# SPI_Expander_MCP29S09.net
KiCad netlist of a schematic drawn in Altium Designer
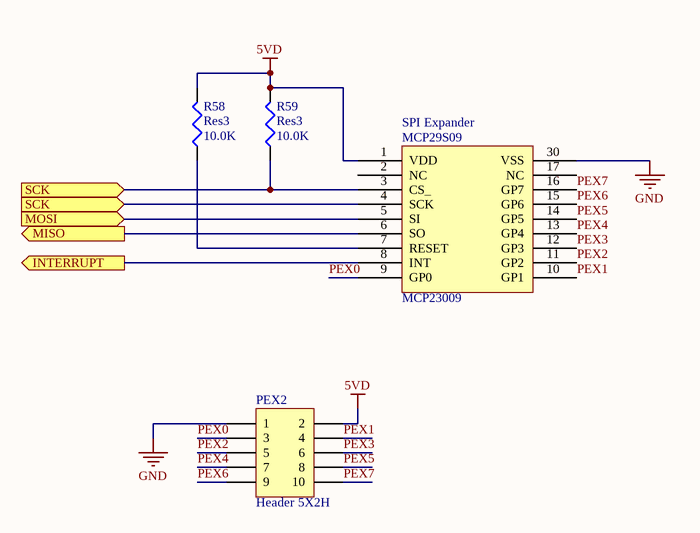
[diagram p0: SPI_Expander_MCP29S09.SchDoc]

(export (version "E")
  (design (tool "Eeschema 10.0.6"))
  (components
    (comp (ref "PEX2")
      (value "Header 5X2H")
      (footprint "HDR2X5H")
      (description "Header, 5-Pin, Dual row, Right Angle")
      (fields (field (name "PUBLISHER") "Altium Limited"))
      (libsource (lib "Miscellaneous Connectors") (part "Header 5X2H"))
    )
    (comp (ref "R58")
      (value "Res3")
      (footprint "RESC2112X05M")
      (description "RES SMD 10.0K OHM 1% 1/8W 0805")
      (fields (field (name "ALTIUM_VALUE") "10.0K") (field (name "MPN") "CRCW080510K0FKEA"))
      (libsource (lib "esd_library") (part "Resistor_10.0K"))
    )
    (comp (ref "R59")
      (value "Res3")
      (footprint "RESC2112X05M")
      (description "RES SMD 10.0K OHM 1% 1/8W 0805")
      (fields (field (name "ALTIUM_VALUE") "10.0K") (field (name "MPN") "CRCW080510K0FKEA"))
      (libsource (lib "esd_library") (part "Resistor_10.0K"))
    )
    (comp (ref "SPI Expander")
      (value "MCP23009")
      (footprint "MCP23009")
      (libsource (lib "Crystal") (part "MCP23009"))
    )
  )
  (nets
    (net (code "1") (name "/INTERRUPT") (class "Default")
      (node (ref "SPI Expander") (pin "8") (pinfunction "INT_8") (pintype "passive"))
    )
    (net (code "2") (name "/MISO") (class "Default")
      (node (ref "SPI Expander") (pin "6") (pinfunction "SO_6") (pintype "passive"))
    )
    (net (code "3") (name "/MOSI") (class "Default")
      (node (ref "SPI Expander") (pin "5") (pinfunction "SI_5") (pintype "passive"))
    )
    (net (code "4") (name "/PEX0") (class "Default")
      (node (ref "PEX2") (pin "3") (pinfunction "3_3") (pintype "passive"))
      (node (ref "SPI Expander") (pin "9") (pinfunction "GP0_9") (pintype "passive"))
    )
    (net (code "5") (name "/PEX1") (class "Default")
      (node (ref "PEX2") (pin "4") (pinfunction "4_4") (pintype "passive"))
      (node (ref "SPI Expander") (pin "10") (pinfunction "GP1_10") (pintype "passive"))
    )
    (net (code "6") (name "/PEX2") (class "Default")
      (node (ref "PEX2") (pin "5") (pinfunction "5_5") (pintype "passive"))
      (node (ref "SPI Expander") (pin "11") (pinfunction "GP2_11") (pintype "passive"))
    )
    (net (code "7") (name "/PEX3") (class "Default")
      (node (ref "PEX2") (pin "6") (pinfunction "6_6") (pintype "passive"))
      (node (ref "SPI Expander") (pin "12") (pinfunction "GP3_12") (pintype "passive"))
    )
    (net (code "8") (name "/PEX4") (class "Default")
      (node (ref "PEX2") (pin "7") (pinfunction "7_7") (pintype "passive"))
      (node (ref "SPI Expander") (pin "13") (pinfunction "GP4_13") (pintype "passive"))
    )
    (net (code "9") (name "/PEX5") (class "Default")
      (node (ref "PEX2") (pin "8") (pinfunction "8_8") (pintype "passive"))
      (node (ref "SPI Expander") (pin "14") (pinfunction "GP5_14") (pintype "passive"))
    )
    (net (code "10") (name "/PEX6") (class "Default")
      (node (ref "PEX2") (pin "9") (pinfunction "9_9") (pintype "passive"))
      (node (ref "SPI Expander") (pin "15") (pinfunction "GP6_15") (pintype "passive"))
    )
    (net (code "11") (name "/PEX7") (class "Default")
      (node (ref "PEX2") (pin "10") (pinfunction "10_10") (pintype "passive"))
      (node (ref "SPI Expander") (pin "16") (pinfunction "GP7_16") (pintype "passive"))
    )
    (net (code "12") (name "/SCK") (class "Default")
      (node (ref "R59") (pin "1") (pinfunction "1_1") (pintype "passive"))
      (node (ref "SPI Expander") (pin "3") (pinfunction "CS__3") (pintype "passive"))
      (node (ref "SPI Expander") (pin "4") (pinfunction "SCK_4") (pintype "passive"))
    )
    (net (code "13") (name "5VD") (class "Default")
      (node (ref "PEX2") (pin "2") (pinfunction "2_2") (pintype "passive"))
      (node (ref "R58") (pin "2") (pinfunction "2_2") (pintype "passive"))
      (node (ref "R59") (pin "2") (pinfunction "2_2") (pintype "passive"))
      (node (ref "SPI Expander") (pin "1") (pinfunction "VDD_1") (pintype "passive"))
    )
    (net (code "14") (name "GND") (class "Default")
      (node (ref "PEX2") (pin "1") (pinfunction "1_1") (pintype "passive"))
      (node (ref "SPI Expander") (pin "30") (pinfunction "VSS_30") (pintype "passive"))
    )
    (net (code "15") (name "Net-(SPI Expander-RESET)") (class "Default")
      (node (ref "R58") (pin "1") (pinfunction "1_1") (pintype "passive"))
      (node (ref "SPI Expander") (pin "7") (pinfunction "RESET_7") (pintype "passive"))
    )
    (net (code "16") (name "unconnected-(SPI Expander-NC-Pad2)") (class "Default")
      (node (ref "SPI Expander") (pin "2") (pinfunction "NC_2") (pintype "passive"))
    )
    (net (code "17") (name "unconnected-(SPI Expander-NC-Pad17)") (class "Default")
      (node (ref "SPI Expander") (pin "17") (pinfunction "NC_17") (pintype "passive"))
    )
  )
)
